# TOP.net
KiCad netlist of a schematic drawn in Altium Designer
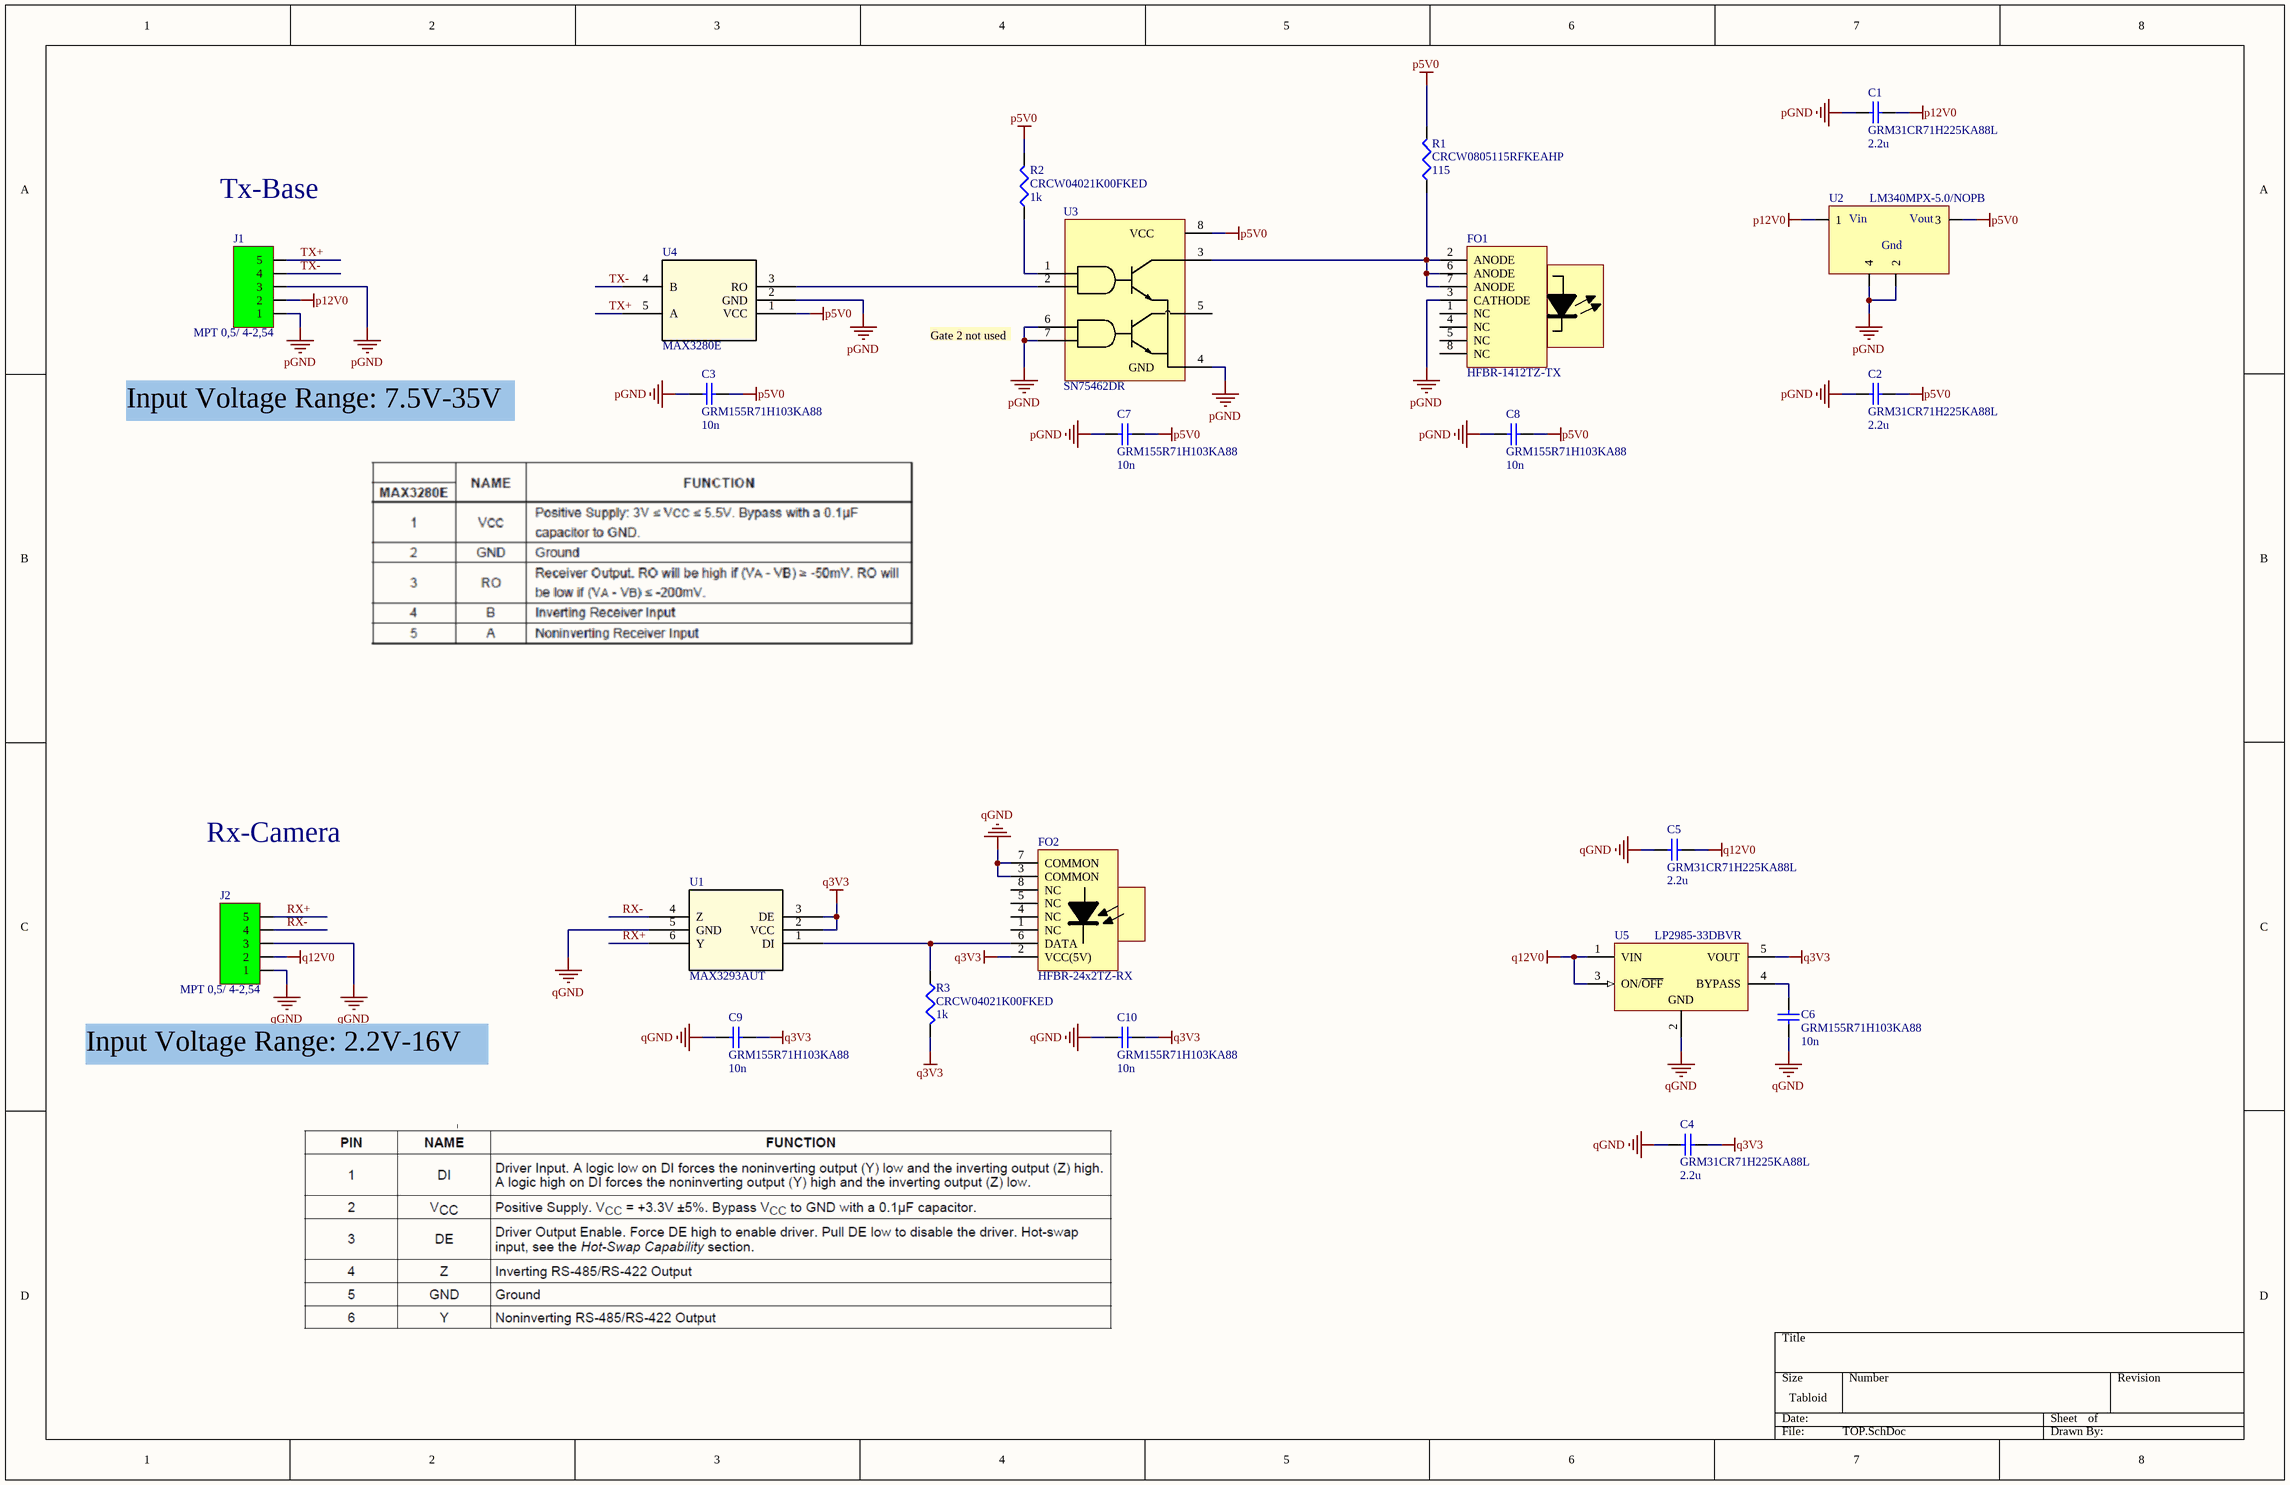
[diagram p0: TOP.SchDoc]

(export (version "E")
  (design (tool "Eeschema 10.0.6"))
  (components
    (comp (ref "C1")
      (value "GRM31CR71H225KA88L")
      (footprint "1206")
      (description "-55-125C, 3216, 50V, X7R, ±10%")
      (fields (field (name "ALTIUM_VALUE") "2.2u"))
      (libsource (lib "standard_capacitors") (part "GRM31CR71HxxxKdddd"))
    )
    (comp (ref "C2")
      (value "GRM31CR71H225KA88L")
      (footprint "1206")
      (description "-55-125C, 3216, 50V, X7R, ±10%")
      (fields (field (name "ALTIUM_VALUE") "2.2u"))
      (libsource (lib "standard_capacitors") (part "GRM31CR71HxxxKdddd"))
    )
    (comp (ref "C3")
      (value "GRM155R71H103KA88")
      (footprint "0402")
      (description "-55-125C, 1005, 50V, X7R, ±10%")
      (fields (field (name "ALTIUM_VALUE") "10n"))
      (libsource (lib "standard_capacitors") (part "GRM155R71HxxxKdddd"))
    )
    (comp (ref "C4")
      (value "GRM31CR71H225KA88L")
      (footprint "1206")
      (description "-55-125C, 3216, 50V, X7R, ±10%")
      (fields (field (name "ALTIUM_VALUE") "2.2u"))
      (libsource (lib "standard_capacitors") (part "GRM31CR71HxxxKdddd"))
    )
    (comp (ref "C5")
      (value "GRM31CR71H225KA88L")
      (footprint "1206")
      (description "-55-125C, 3216, 50V, X7R, ±10%")
      (fields (field (name "ALTIUM_VALUE") "2.2u"))
      (libsource (lib "standard_capacitors") (part "GRM31CR71HxxxKdddd"))
    )
    (comp (ref "C6")
      (value "GRM155R71H103KA88")
      (footprint "0402")
      (description "-55-125C, 1005, 50V, X7R, ±10%")
      (fields (field (name "ALTIUM_VALUE") "10n"))
      (libsource (lib "standard_capacitors") (part "GRM155R71HxxxKdddd"))
    )
    (comp (ref "C7")
      (value "GRM155R71H103KA88")
      (footprint "0402")
      (description "-55-125C, 1005, 50V, X7R, ±10%")
      (fields (field (name "ALTIUM_VALUE") "10n"))
      (libsource (lib "standard_capacitors") (part "GRM155R71HxxxKdddd"))
    )
    (comp (ref "C8")
      (value "GRM155R71H103KA88")
      (footprint "0402")
      (description "-55-125C, 1005, 50V, X7R, ±10%")
      (fields (field (name "ALTIUM_VALUE") "10n"))
      (libsource (lib "standard_capacitors") (part "GRM155R71HxxxKdddd"))
    )
    (comp (ref "C9")
      (value "GRM155R71H103KA88")
      (footprint "0402")
      (description "-55-125C, 1005, 50V, X7R, ±10%")
      (fields (field (name "ALTIUM_VALUE") "10n"))
      (libsource (lib "standard_capacitors") (part "GRM155R71HxxxKdddd"))
    )
    (comp (ref "C10")
      (value "GRM155R71H103KA88")
      (footprint "0402")
      (description "-55-125C, 1005, 50V, X7R, ±10%")
      (fields (field (name "ALTIUM_VALUE") "10n"))
      (libsource (lib "standard_capacitors") (part "GRM155R71HxxxKdddd"))
    )
    (comp (ref "FO1")
      (value "HFBR-1412TZ-TX")
      (footprint "HFBR-x41xTZ")
      (description "HFBR-14x2TZ-TX fiber optic threaded ST port")
      (libsource (lib "avago") (part "HFBR-14x2TZ-TX"))
    )
    (comp (ref "FO2")
      (value "HFBR-24x2TZ-RX")
      (footprint "HFBR-x41xTZ")
      (description "HFBR-24x2TZ-RX fiber optic ST receiver")
      (libsource (lib "avago") (part "HFBR-24x2TZ-RX"))
    )
    (comp (ref "J1")
      (value "MPT 0,5/ 4-2,54")
      (footprint "MPT 0,5/ 5-2,54")
      (libsource (lib "phoenix_contact") (part "MPT 0,5/ 5-2,54"))
    )
    (comp (ref "J2")
      (value "MPT 0,5/ 4-2,54")
      (footprint "MPT 0,5/ 5-2,54")
      (libsource (lib "phoenix_contact") (part "MPT 0,5/ 5-2,54"))
    )
    (comp (ref "R1")
      (value "CRCW0805115RFKEAHP")
      (footprint "0805")
      (description "0.125W, -55-155C, 1005, 50V, ±1%")
      (fields (field (name "ALTIUM_VALUE") "115"))
      (libsource (lib "standard_resistors") (part "R-MISC"))
    )
    (comp (ref "R2")
      (value "CRCW04021K00FKED")
      (footprint "0402")
      (description "0.125W, -55-155C, 1005, 50V, ±1%")
      (fields (field (name "ALTIUM_VALUE") "1k"))
      (libsource (lib "standard_resistors") (part "CRCW0402xxxxFKED"))
    )
    (comp (ref "R3")
      (value "CRCW04021K00FKED")
      (footprint "0402")
      (description "0.125W, -55-155C, 1005, 50V, ±1%")
      (fields (field (name "ALTIUM_VALUE") "1k"))
      (libsource (lib "standard_resistors") (part "CRCW0402xxxxFKED"))
    )
    (comp (ref "U1")
      (value "MAX3293AUT")
      (footprint "SOT23-6")
      (description "No Description Available")
      (fields
        (field (name "MANUFACTURER_PART_NUMBER") "MAX3293AUT+")
        (field (name "COPYRIGHT") "Copyright (C) 2018 Accelerated Designs. All rights reserved")
      )
      (libsource (lib "maxim") (part "MAX3293AUT"))
    )
    (comp (ref "U2")
      (value "LM340MPX-5.0/NOPB")
      (footprint "LM340MPX-5.0/NOPB")
      (libsource (lib "texas_instruments") (part "LM340MPX-5.0/NOPB"))
    )
    (comp (ref "U3")
      (value "SN75462DR")
      (footprint "SOP-8")
      (description "NAND Dual Peripheral drivers, SMT")
      (libsource (lib "texas_instruments") (part "SN75462DR"))
    )
    (comp (ref "U4")
      (value "MAX3280E")
      (footprint "SOT23-5")
      (fields
        (field (name "MANUFACTURER_PART_NUMBER") "MAX3293AUT+")
        (field (name "COPYRIGHT") "Copyright (C) 2018 Accelerated Designs. All rights reserved")
      )
      (libsource (lib "maxim") (part "MAX3280E"))
    )
    (comp (ref "U5")
      (value "LP2985-33DBVR")
      (footprint "TI-DBV5_V")
      (fields (field (name "MANUFACTURER") "Texas Instruments"))
      (libsource (lib "Brandon Dixon") (part "TI-LP2985_A-DBV-5"))
    )
  )
  (nets
    (net (code "1") (name "/RX+") (class "Default")
      (node (ref "J2") (pin "5") (pinfunction "5_5") (pintype "passive"))
      (node (ref "U1") (pin "6") (pinfunction "Y_6") (pintype "passive"))
    )
    (net (code "2") (name "/RX-") (class "Default")
      (node (ref "J2") (pin "4") (pinfunction "4_4") (pintype "passive"))
      (node (ref "U1") (pin "4") (pinfunction "Z_4") (pintype "passive"))
    )
    (net (code "3") (name "/TX+") (class "Default")
      (node (ref "J1") (pin "5") (pinfunction "5_5") (pintype "passive"))
      (node (ref "U4") (pin "5") (pinfunction "A_5") (pintype "power_in"))
    )
    (net (code "4") (name "/TX-") (class "Default")
      (node (ref "J1") (pin "4") (pinfunction "4_4") (pintype "passive"))
      (node (ref "U4") (pin "4") (pinfunction "B_4") (pintype "passive"))
    )
    (net (code "5") (name "Net-(FO2-DATA)") (class "Default")
      (node (ref "FO2") (pin "6") (pinfunction "DATA_6") (pintype "open_collector"))
      (node (ref "R3") (pin "1") (pinfunction "1_1") (pintype "passive"))
      (node (ref "U1") (pin "1") (pinfunction "DI_1") (pintype "passive"))
    )
    (net (code "6") (name "Net-(U3-1A)") (class "Default")
      (node (ref "R2") (pin "1") (pinfunction "1_1") (pintype "passive"))
      (node (ref "U3") (pin "1") (pinfunction "1A_1") (pintype "passive"))
    )
    (net (code "7") (name "Net-(U3-1B)") (class "Default")
      (node (ref "U3") (pin "2") (pinfunction "1B_2") (pintype "passive"))
      (node (ref "U4") (pin "3") (pinfunction "RO_3") (pintype "passive"))
    )
    (net (code "8") (name "Net-(U3-1Y)") (class "Default")
      (node (ref "FO1") (pin "2") (pinfunction "ANODE_2") (pintype "passive"))
      (node (ref "FO1") (pin "6") (pinfunction "ANODE_6") (pintype "passive"))
      (node (ref "FO1") (pin "7") (pinfunction "ANODE_7") (pintype "passive"))
      (node (ref "R1") (pin "1") (pinfunction "1_1") (pintype "passive"))
      (node (ref "U3") (pin "3") (pinfunction "1Y_3") (pintype "passive"))
    )
    (net (code "9") (name "Net-(U5-BYPASS)") (class "Default")
      (node (ref "C6") (pin "2") (pinfunction "2_2") (pintype "passive"))
      (node (ref "U5") (pin "4") (pinfunction "BYPASS_4") (pintype "passive"))
    )
    (net (code "10") (name "p5V0") (class "Default")
      (node (ref "C2") (pin "2") (pinfunction "2_2") (pintype "passive"))
      (node (ref "C3") (pin "2") (pinfunction "2_2") (pintype "passive"))
      (node (ref "C7") (pin "2") (pinfunction "2_2") (pintype "passive"))
      (node (ref "C8") (pin "2") (pinfunction "2_2") (pintype "passive"))
      (node (ref "R1") (pin "2") (pinfunction "2_2") (pintype "passive"))
      (node (ref "R2") (pin "2") (pinfunction "2_2") (pintype "passive"))
      (node (ref "U2") (pin "3") (pinfunction "3_3") (pintype "passive"))
      (node (ref "U3") (pin "8") (pinfunction "VCC_8") (pintype "passive"))
      (node (ref "U4") (pin "1") (pinfunction "VCC_1") (pintype "passive"))
    )
    (net (code "11") (name "p12V0") (class "Default")
      (node (ref "C1") (pin "2") (pinfunction "2_2") (pintype "passive"))
      (node (ref "J1") (pin "2") (pinfunction "2_2") (pintype "passive"))
      (node (ref "U2") (pin "1") (pinfunction "1_1") (pintype "passive"))
    )
    (net (code "12") (name "pGND") (class "Default")
      (node (ref "C1") (pin "1") (pinfunction "1_1") (pintype "passive"))
      (node (ref "C2") (pin "1") (pinfunction "1_1") (pintype "passive"))
      (node (ref "C3") (pin "1") (pinfunction "1_1") (pintype "passive"))
      (node (ref "C7") (pin "1") (pinfunction "1_1") (pintype "passive"))
      (node (ref "C8") (pin "1") (pinfunction "1_1") (pintype "passive"))
      (node (ref "FO1") (pin "3") (pinfunction "CATHODE_3") (pintype "passive"))
      (node (ref "J1") (pin "1") (pinfunction "1_1") (pintype "passive"))
      (node (ref "J1") (pin "3") (pinfunction "3_3") (pintype "passive"))
      (node (ref "U2") (pin "2") (pinfunction "2_2") (pintype "passive"))
      (node (ref "U2") (pin "4") (pinfunction "4_4") (pintype "passive"))
      (node (ref "U3") (pin "4") (pinfunction "GND_4") (pintype "passive"))
      (node (ref "U3") (pin "6") (pinfunction "2A_6") (pintype "passive"))
      (node (ref "U3") (pin "7") (pinfunction "2B_7") (pintype "passive"))
      (node (ref "U4") (pin "2") (pinfunction "GND_2") (pintype "power_in"))
    )
    (net (code "13") (name "q3V3") (class "Default")
      (node (ref "C10") (pin "2") (pinfunction "2_2") (pintype "passive"))
      (node (ref "C4") (pin "2") (pinfunction "2_2") (pintype "passive"))
      (node (ref "C9") (pin "2") (pinfunction "2_2") (pintype "passive"))
      (node (ref "FO2") (pin "2") (pinfunction "VCC(5V)_2") (pintype "passive"))
      (node (ref "R3") (pin "2") (pinfunction "2_2") (pintype "passive"))
      (node (ref "U1") (pin "2") (pinfunction "VCC_2") (pintype "power_in"))
      (node (ref "U1") (pin "3") (pinfunction "DE_3") (pintype "passive"))
      (node (ref "U5") (pin "5") (pinfunction "VOUT_5") (pintype "power_in"))
    )
    (net (code "14") (name "q12V0") (class "Default")
      (node (ref "C5") (pin "2") (pinfunction "2_2") (pintype "passive"))
      (node (ref "J2") (pin "2") (pinfunction "2_2") (pintype "passive"))
      (node (ref "U5") (pin "1") (pinfunction "VIN_1") (pintype "power_in"))
      (node (ref "U5") (pin "3") (pinfunction "ON/~{OFF}_3") (pintype "input"))
    )
    (net (code "15") (name "qGND") (class "Default")
      (node (ref "C10") (pin "1") (pinfunction "1_1") (pintype "passive"))
      (node (ref "C4") (pin "1") (pinfunction "1_1") (pintype "passive"))
      (node (ref "C5") (pin "1") (pinfunction "1_1") (pintype "passive"))
      (node (ref "C6") (pin "1") (pinfunction "1_1") (pintype "passive"))
      (node (ref "C9") (pin "1") (pinfunction "1_1") (pintype "passive"))
      (node (ref "FO2") (pin "3") (pinfunction "COMMON_3") (pintype "passive"))
      (node (ref "FO2") (pin "7") (pinfunction "COMMON_7") (pintype "passive"))
      (node (ref "J2") (pin "1") (pinfunction "1_1") (pintype "passive"))
      (node (ref "J2") (pin "3") (pinfunction "3_3") (pintype "passive"))
      (node (ref "U1") (pin "5") (pinfunction "GND_5") (pintype "power_in"))
      (node (ref "U5") (pin "2") (pinfunction "GND_2") (pintype "power_in"))
    )
    (net (code "16") (name "unconnected-(FO1-NC-Pad1)") (class "Default")
      (node (ref "FO1") (pin "1") (pinfunction "NC_1") (pintype "passive"))
    )
    (net (code "17") (name "unconnected-(FO1-NC-Pad4)") (class "Default")
      (node (ref "FO1") (pin "4") (pinfunction "NC_4") (pintype "passive"))
    )
    (net (code "18") (name "unconnected-(FO1-NC-Pad5)") (class "Default")
      (node (ref "FO1") (pin "5") (pinfunction "NC_5") (pintype "passive"))
    )
    (net (code "19") (name "unconnected-(FO1-NC-Pad8)") (class "Default")
      (node (ref "FO1") (pin "8") (pinfunction "NC_8") (pintype "passive"))
    )
    (net (code "20") (name "unconnected-(FO2-NC-Pad1)") (class "Default")
      (node (ref "FO2") (pin "1") (pinfunction "NC_1") (pintype "passive"))
    )
    (net (code "21") (name "unconnected-(FO2-NC-Pad4)") (class "Default")
      (node (ref "FO2") (pin "4") (pinfunction "NC_4") (pintype "passive"))
    )
    (net (code "22") (name "unconnected-(FO2-NC-Pad5)") (class "Default")
      (node (ref "FO2") (pin "5") (pinfunction "NC_5") (pintype "passive"))
    )
    (net (code "23") (name "unconnected-(FO2-NC-Pad8)") (class "Default")
      (node (ref "FO2") (pin "8") (pinfunction "NC_8") (pintype "passive"))
    )
    (net (code "24") (name "unconnected-(U3-2Y-Pad5)") (class "Default")
      (node (ref "U3") (pin "5") (pinfunction "2Y_5") (pintype "passive"))
    )
  )
)
